# SCH_PCB-JaydenB-Hacker-Card.net
KiCad netlist of a schematic drawn in EasyEDA
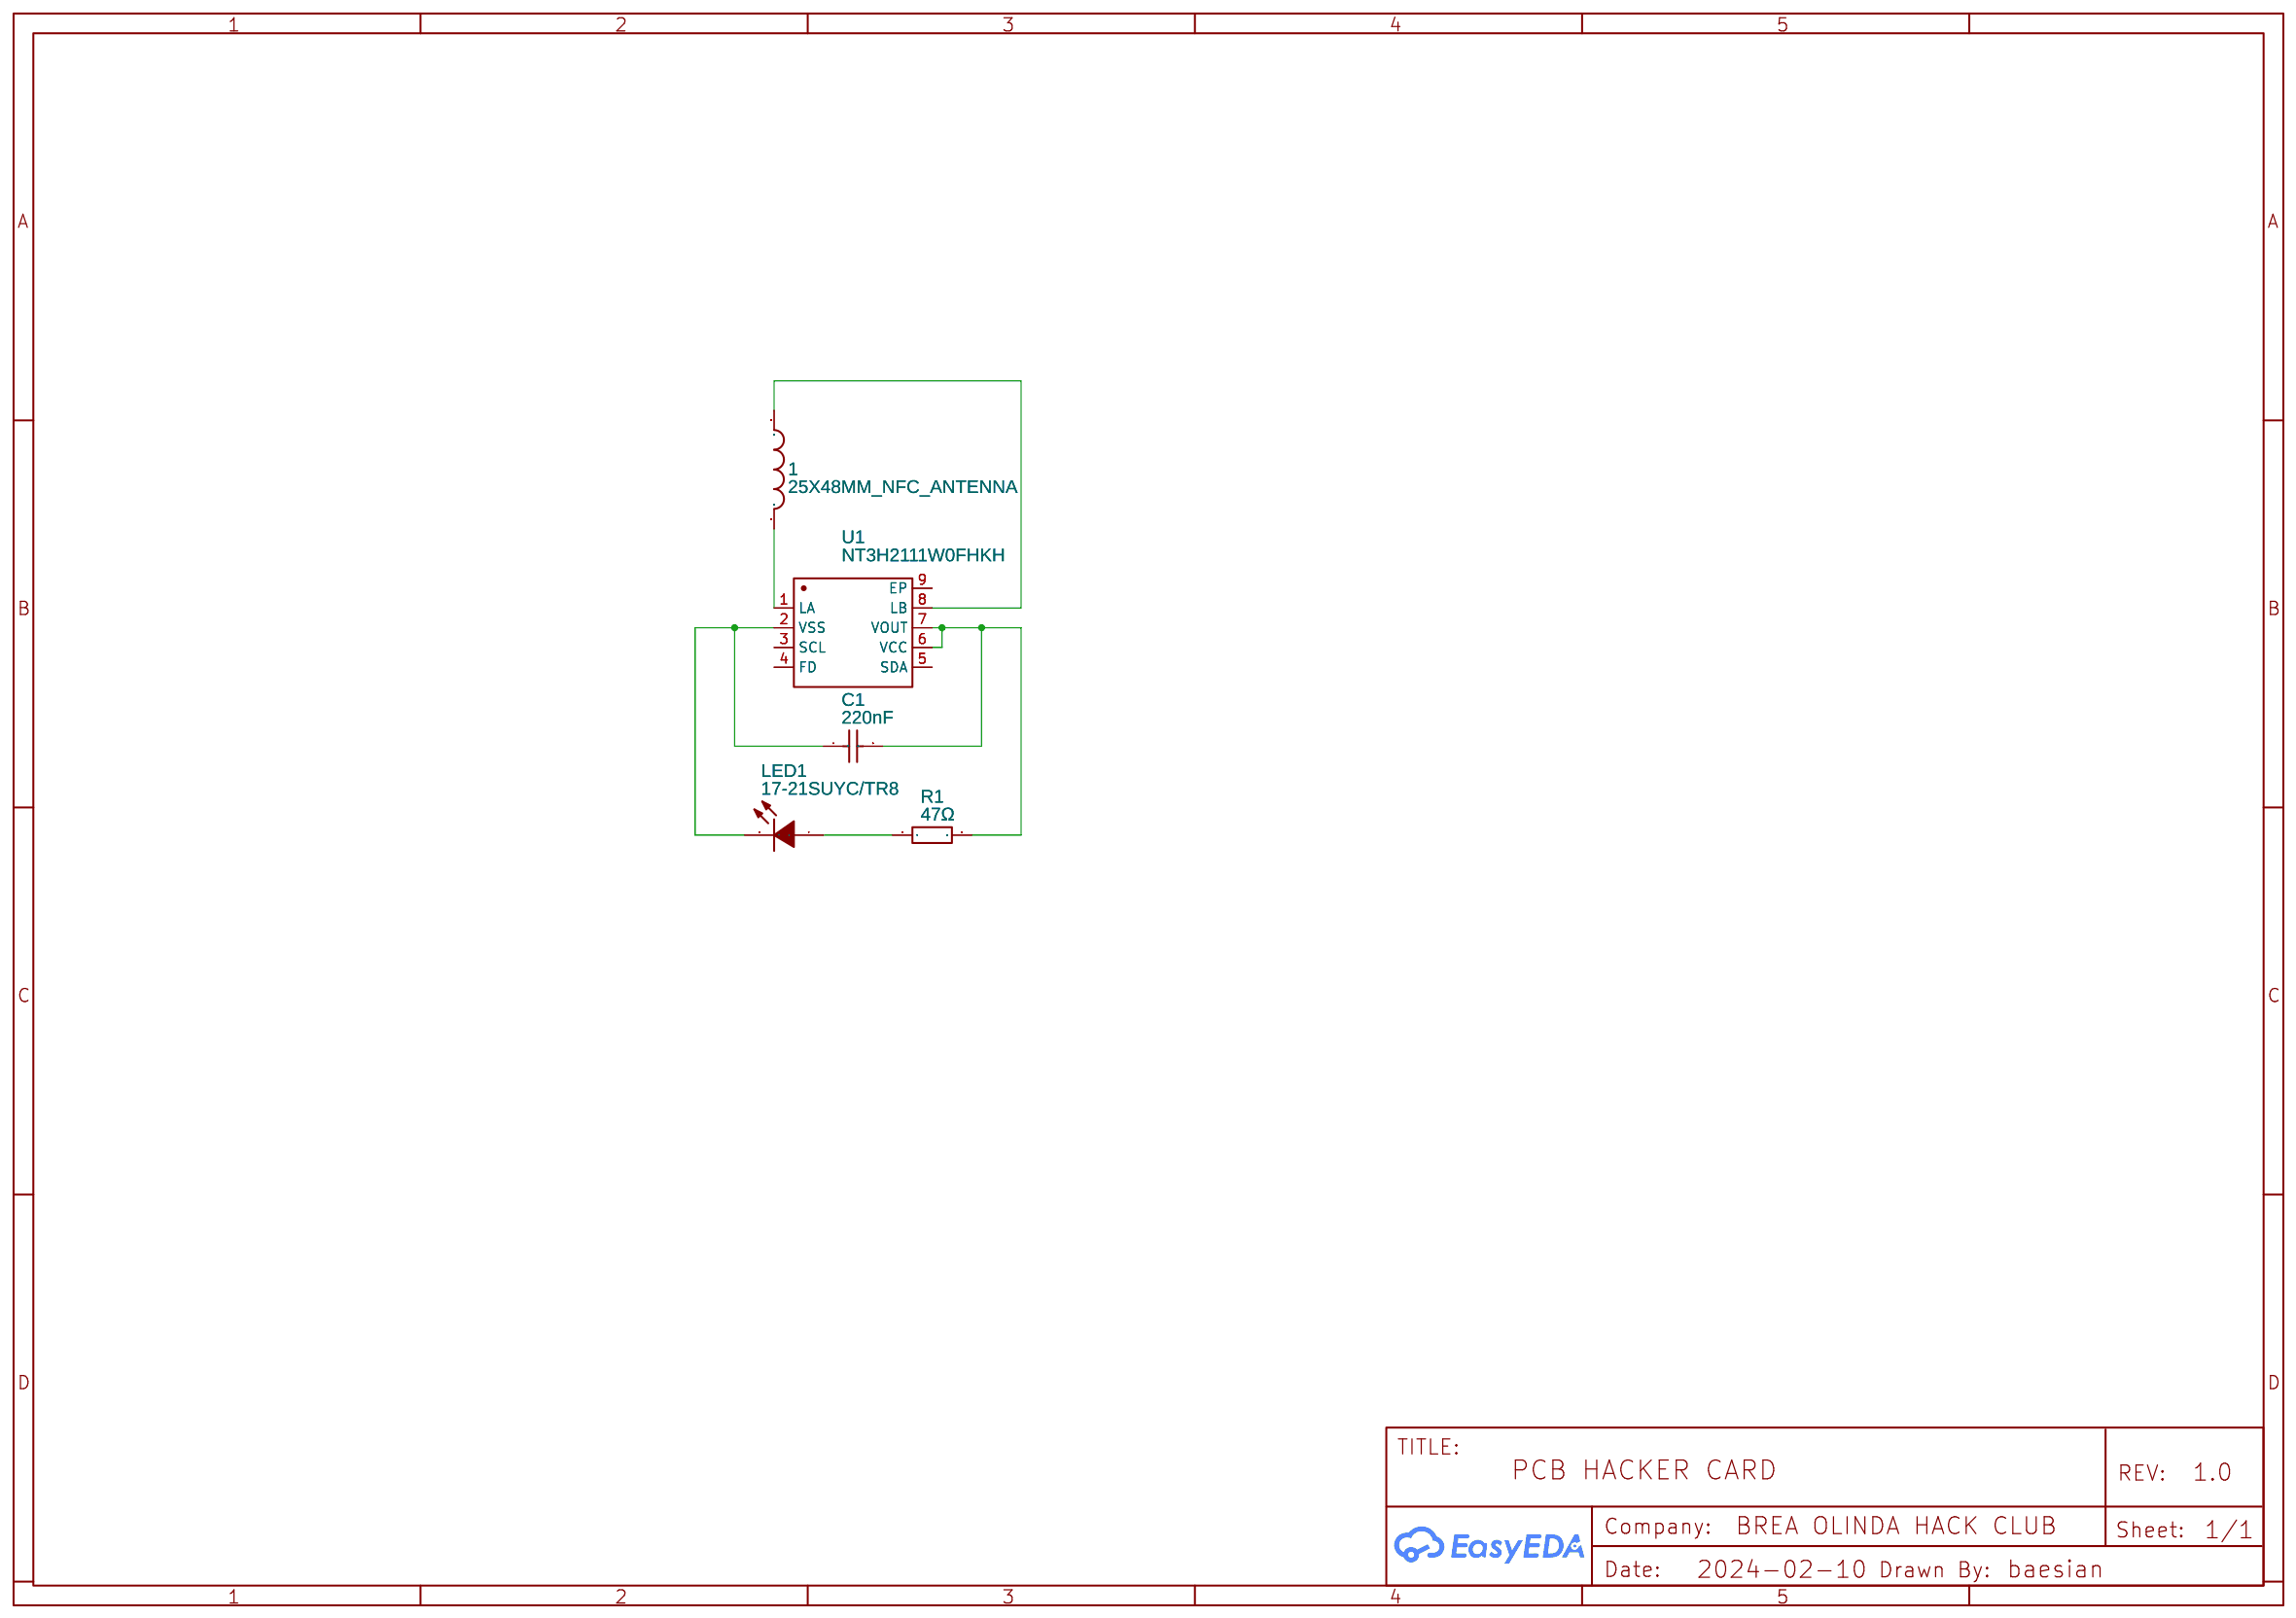
[diagram p0: schematic sheet]

(export (version "E")
  (design (tool "Eeschema 10.0.6"))
  (components
    (comp (ref "1") (value "25X48MM_NFC_ANTENNA") (libsource (lib "") (part "25X48MM_NFC_ANTENNA")))
    (comp (ref "C1")
      (value "220nF")
      (fields
        (field (name "Manufacturer Part") "CL10B224KA8NNNC")
        (field (name "Manufacturer") "SAMSUNG(三星)")
      )
      (libsource (lib "") (part "CL10B224KA8NNNC"))
    )
    (comp (ref "LED1")
      (value "17-21SUYC/TR8")
      (fields (field (name "Manufacturer Part") "KT-0805黄灯") (field (name "Manufacturer") "KENTO"))
      (libsource (lib "") (part "17-21SUYC/TR8"))
    )
    (comp (ref "R1")
      (value "47Ω")
      (fields
        (field (name "Manufacturer Part") "0603WAF470JT5E")
        (field (name "Manufacturer") "UNI-ROYAL(厚声)")
      )
      (libsource (lib "") (part "0603WAF470JT5E"))
    )
    (comp (ref "U1")
      (value "NT3H2111W0FHKH")
      (fields (field (name "Manufacturer") "NXP(恩智浦)"))
      (libsource (lib "") (part "NT3H2111W0FHKH"))
    )
  )
  (nets
    (net (code "1") (name "Net-(LED1-+)") (class "Default")
      (node (ref "LED1") (pin "1") (pinfunction "+_1") (pintype "unspecified"))
      (node (ref "R1") (pin "1") (pinfunction "1_1") (pintype "input"))
    )
    (net (code "2") (name "Net-(LED1--)") (class "Default")
      (node (ref "C1") (pin "1") (pinfunction "1_1") (pintype "input"))
      (node (ref "LED1") (pin "2") (pinfunction "-_2") (pintype "unspecified"))
      (node (ref "U1") (pin "2") (pinfunction "VSS_2") (pintype "unspecified"))
    )
    (net (code "3") (name "Net-(U1-LA)") (class "Default")
      (node (ref "1") (pin "P$2") (pinfunction "P$2_P$2") (pintype "bidirectional"))
      (node (ref "U1") (pin "1") (pinfunction "LA_1") (pintype "unspecified"))
    )
    (net (code "4") (name "Net-(U1-LB)") (class "Default")
      (node (ref "1") (pin "P$1") (pinfunction "P$1_P$1") (pintype "bidirectional"))
      (node (ref "U1") (pin "8") (pinfunction "LB_8") (pintype "unspecified"))
    )
    (net (code "5") (name "Net-(U1-VCC)") (class "Default")
      (node (ref "C1") (pin "2") (pinfunction "2_2") (pintype "input"))
      (node (ref "R1") (pin "2") (pinfunction "2_2") (pintype "input"))
      (node (ref "U1") (pin "6") (pinfunction "VCC_6") (pintype "unspecified"))
      (node (ref "U1") (pin "7") (pinfunction "VOUT_7") (pintype "unspecified"))
    )
    (net (code "6") (name "unconnected-(U1-EP-Pad9)") (class "Default")
      (node (ref "U1") (pin "9") (pinfunction "EP_9") (pintype "unspecified"))
    )
    (net (code "7") (name "unconnected-(U1-FD-Pad4)") (class "Default")
      (node (ref "U1") (pin "4") (pinfunction "FD_4") (pintype "unspecified"))
    )
    (net (code "8") (name "unconnected-(U1-SCL-Pad3)") (class "Default")
      (node (ref "U1") (pin "3") (pinfunction "SCL_3") (pintype "unspecified"))
    )
    (net (code "9") (name "unconnected-(U1-SDA-Pad5)") (class "Default")
      (node (ref "U1") (pin "5") (pinfunction "SDA_5") (pintype "unspecified"))
    )
  )
)
